# Sheet.net
KiCad netlist of a schematic drawn in Altium Designer
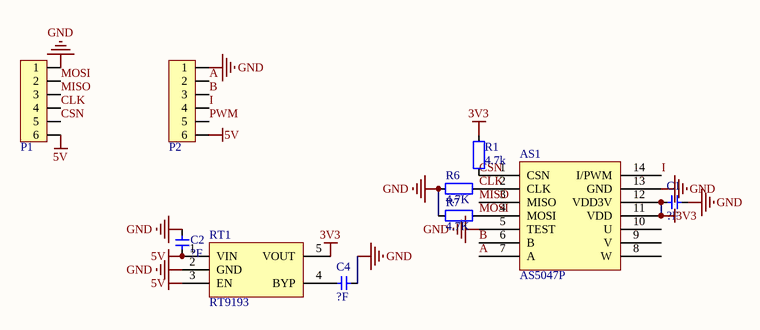
[diagram p0: Sheet.SchDoc]

(export (version "E")
  (design (tool "Eeschema 10.0.6"))
  (components
    (comp (ref "AS1")
      (value "AS5047P")
      (footprint "AS5047P")
      (libsource (lib "SCH_IntegratedCircuit") (part "AS5047P"))
    )
    (comp (ref "C1")
      (value "?F")
      (footprint "PCB_PassiveCap:CAP_0603")
      (description "Capacitor")
      (fields (field (name "Comment") "Cap_0603"))
      (libsource (lib "SCH_Passive") (part "Cap_0603"))
    )
    (comp (ref "C2")
      (value "?F")
      (footprint "PCB_PassiveCap:CAP_0603")
      (description "Capacitor")
      (fields (field (name "Comment") "Cap_0603"))
      (libsource (lib "SCH_Passive") (part "Cap_0603"))
    )
    (comp (ref "C4")
      (value "?F")
      (footprint "PCB_PassiveCap:CAP_0603")
      (description "Capacitor")
      (fields (field (name "Comment") "Cap_0603"))
      (libsource (lib "SCH_Passive") (part "Cap_0603"))
    )
    (comp (ref "P1")
      (value "HDR1x6_2.54")
      (footprint "PCB_ConnectorHDR:1.25mm_1X6_SMT")
      (description "Header")
      (libsource (lib "SCH_ConnectorHDR") (part "HDR1x6_2.54T"))
    )
    (comp (ref "P2")
      (value "HDR1x6_2.54")
      (footprint "PCB_ConnectorHDR:1.25mm_1X6_SMT")
      (description "Header")
      (libsource (lib "SCH_ConnectorHDR") (part "HDR1x6_2.54T"))
    )
    (comp (ref "R1")
      (value "4.7k")
      (footprint "PCB_PassiveRes:RES_0603")
      (description "Resistor")
      (fields (field (name "Comment") "Res_0603"))
      (libsource (lib "") (part "Res_0603_1"))
    )
    (comp (ref "R6")
      (value "4.7K")
      (footprint "PCB_PassiveRes:RES_0603")
      (description "Resistor")
      (fields (field (name "Comment") "Res_0603"))
      (libsource (lib "SCH_Passive") (part "Res_0603"))
    )
    (comp (ref "R7")
      (value "4.7K")
      (footprint "PCB_PassiveRes:RES_0603")
      (description "Resistor")
      (fields (field (name "Comment") "Res_0603"))
      (libsource (lib "SCH_Passive") (part "Res_0603"))
    )
    (comp (ref "RT1")
      (value "RT9193")
      (footprint "PCB_IntegratedCircuit:SOT23-5")
      (description "Power")
      (libsource (lib "SCH_IntegratedCircuit") (part "RT9193"))
    )
  )
  (nets
    (net (code "1") (name "/A") (class "Default")
      (node (ref "AS1") (pin "7") (pinfunction "A_7") (pintype "passive"))
      (node (ref "P2") (pin "2") (pinfunction "2_2") (pintype "passive"))
    )
    (net (code "2") (name "/B") (class "Default")
      (node (ref "AS1") (pin "6") (pinfunction "B_6") (pintype "passive"))
      (node (ref "P2") (pin "3") (pinfunction "3_3") (pintype "passive"))
    )
    (net (code "3") (name "/CLK") (class "Default")
      (node (ref "AS1") (pin "2") (pinfunction "CLK_2") (pintype "passive"))
      (node (ref "P1") (pin "4") (pinfunction "4_4") (pintype "passive"))
      (node (ref "R6") (pin "1") (pinfunction "1_1") (pintype "passive"))
    )
    (net (code "4") (name "/CSN") (class "Default")
      (node (ref "AS1") (pin "1") (pinfunction "CSN_1") (pintype "passive"))
      (node (ref "P1") (pin "5") (pinfunction "5_5") (pintype "passive"))
      (node (ref "R1") (pin "1") (pinfunction "1_1") (pintype "passive"))
    )
    (net (code "5") (name "/I") (class "Default")
      (node (ref "AS1") (pin "14") (pinfunction "I/PWM_14") (pintype "passive"))
      (node (ref "P2") (pin "4") (pinfunction "4_4") (pintype "passive"))
    )
    (net (code "6") (name "/MISO") (class "Default")
      (node (ref "AS1") (pin "3") (pinfunction "MISO_3") (pintype "passive"))
      (node (ref "P1") (pin "3") (pinfunction "3_3") (pintype "passive"))
    )
    (net (code "7") (name "/MOSI") (class "Default")
      (node (ref "AS1") (pin "4") (pinfunction "MOSI_4") (pintype "passive"))
      (node (ref "P1") (pin "2") (pinfunction "2_2") (pintype "passive"))
      (node (ref "R7") (pin "1") (pinfunction "1_1") (pintype "passive"))
    )
    (net (code "8") (name "/PWM") (class "Default")
      (node (ref "P2") (pin "5") (pinfunction "5_5") (pintype "passive"))
    )
    (net (code "9") (name "3V3") (class "Default")
      (node (ref "AS1") (pin "11") (pinfunction "VDD_11") (pintype "passive"))
      (node (ref "AS1") (pin "12") (pinfunction "VDD3V_12") (pintype "passive"))
      (node (ref "C1") (pin "1") (pinfunction "1_1") (pintype "passive"))
      (node (ref "R1") (pin "2") (pinfunction "2_2") (pintype "passive"))
      (node (ref "RT1") (pin "5") (pinfunction "VOUT_5") (pintype "passive"))
    )
    (net (code "10") (name "5V") (class "Default")
      (node (ref "C2") (pin "2") (pinfunction "2_2") (pintype "passive"))
      (node (ref "P1") (pin "6") (pinfunction "6_6") (pintype "passive"))
      (node (ref "P2") (pin "6") (pinfunction "6_6") (pintype "passive"))
      (node (ref "RT1") (pin "1") (pinfunction "VIN_1") (pintype "passive"))
      (node (ref "RT1") (pin "3") (pinfunction "EN_3") (pintype "power_in"))
    )
    (net (code "11") (name "GND") (class "Default")
      (node (ref "AS1") (pin "13") (pinfunction "GND_13") (pintype "passive"))
      (node (ref "AS1") (pin "5") (pinfunction "TEST_5") (pintype "passive"))
      (node (ref "C1") (pin "2") (pinfunction "2_2") (pintype "passive"))
      (node (ref "C2") (pin "1") (pinfunction "1_1") (pintype "passive"))
      (node (ref "C4") (pin "1") (pinfunction "1_1") (pintype "passive"))
      (node (ref "P1") (pin "1") (pinfunction "1_1") (pintype "passive"))
      (node (ref "P2") (pin "1") (pinfunction "1_1") (pintype "passive"))
      (node (ref "R6") (pin "2") (pinfunction "2_2") (pintype "passive"))
      (node (ref "R7") (pin "2") (pinfunction "2_2") (pintype "passive"))
      (node (ref "RT1") (pin "2") (pinfunction "GND_2") (pintype "passive"))
    )
    (net (code "12") (name "Net-(RT1-BYP)") (class "Default")
      (node (ref "C4") (pin "2") (pinfunction "2_2") (pintype "passive"))
      (node (ref "RT1") (pin "4") (pinfunction "BYP_4") (pintype "passive"))
    )
    (net (code "13") (name "unconnected-(AS1-U-Pad10)") (class "Default")
      (node (ref "AS1") (pin "10") (pinfunction "U_10") (pintype "passive"))
    )
    (net (code "14") (name "unconnected-(AS1-V-Pad9)") (class "Default")
      (node (ref "AS1") (pin "9") (pinfunction "V_9") (pintype "passive"))
    )
    (net (code "15") (name "unconnected-(AS1-W-Pad8)") (class "Default")
      (node (ref "AS1") (pin "8") (pinfunction "W_8") (pintype "passive"))
    )
  )
)
